# FIDO2AUTH_0021.net
KiCad netlist of a schematic drawn in EAGLE
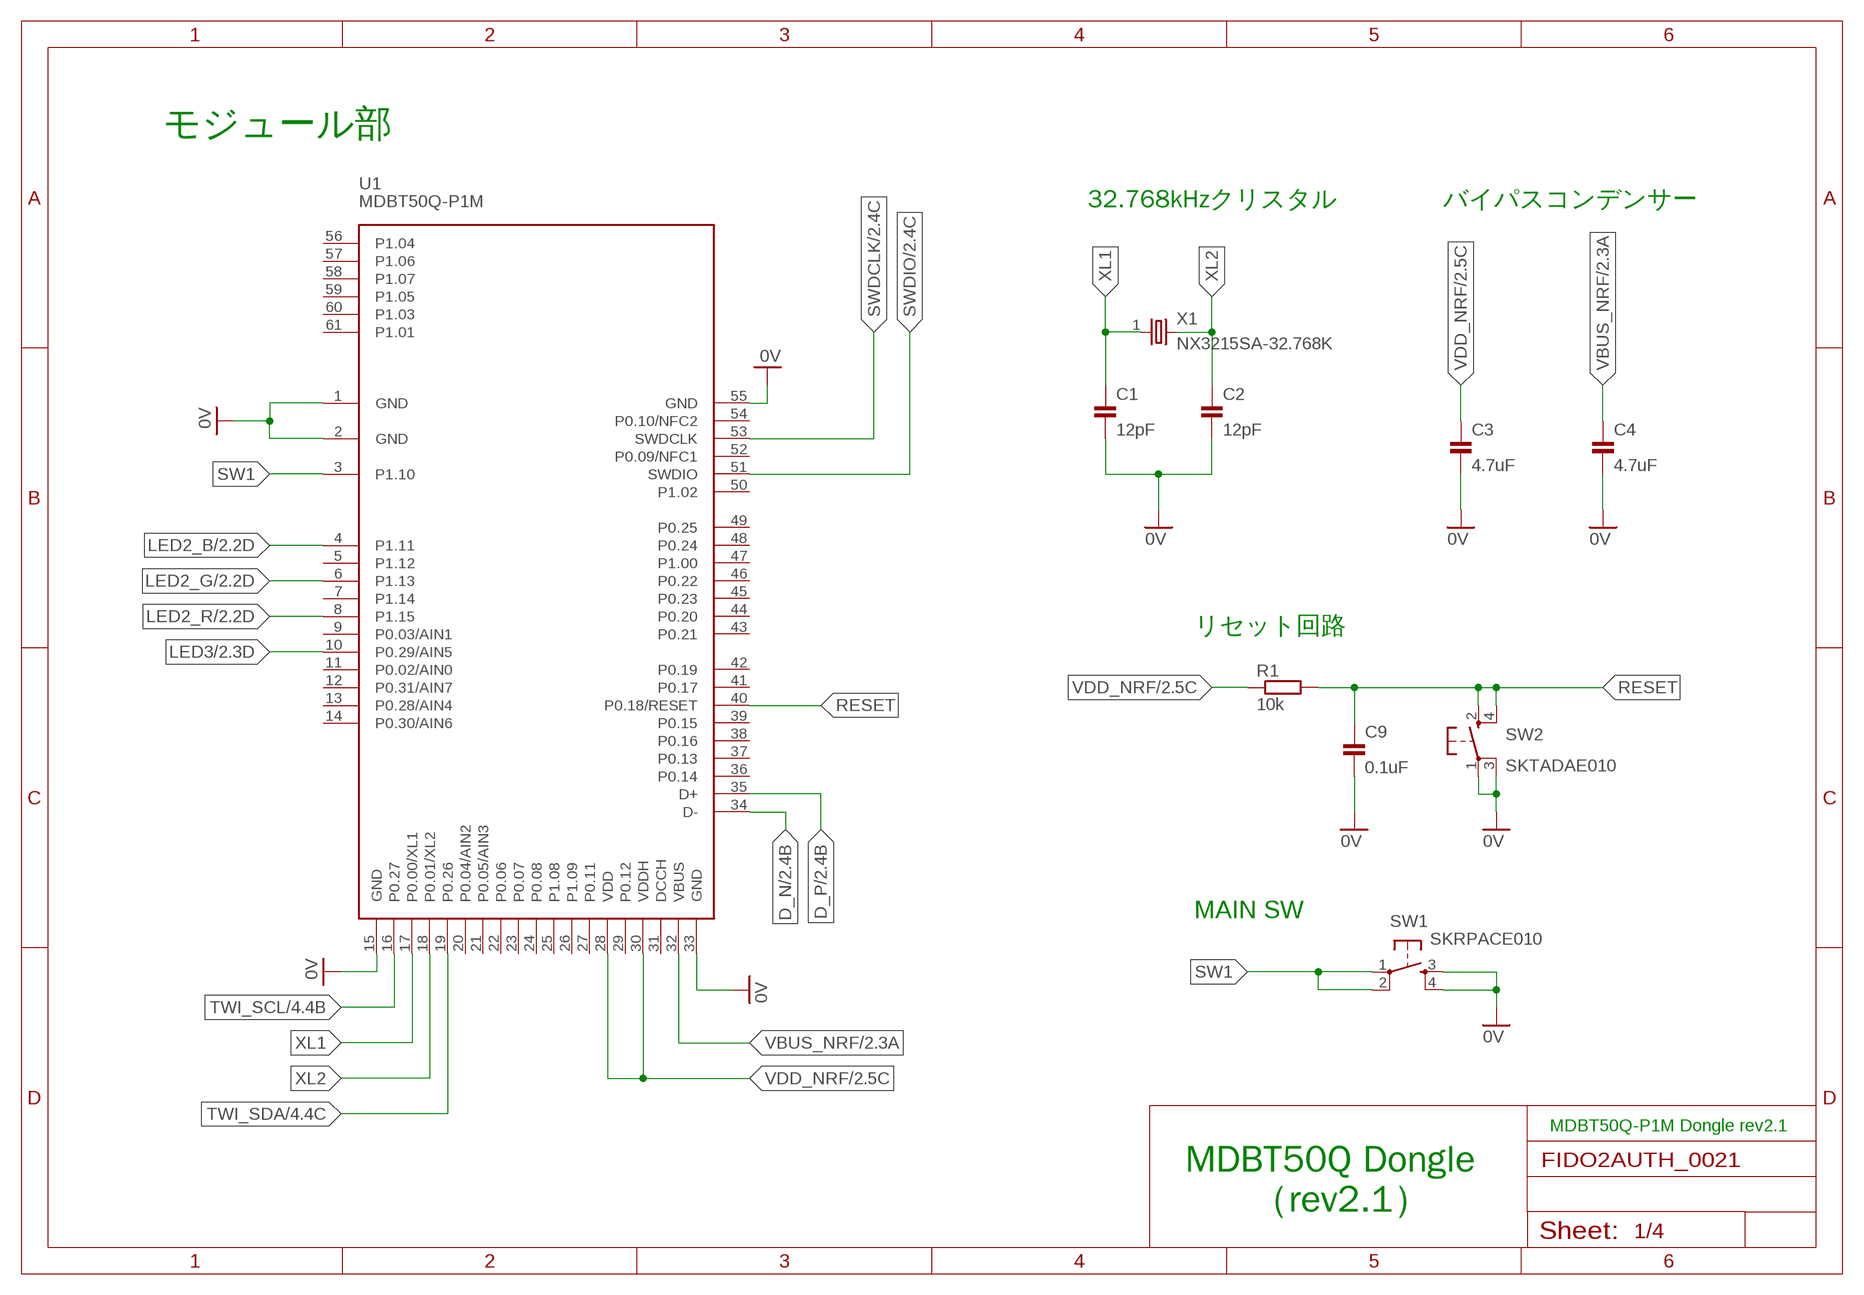
[diagram p0: schematic, sheet 1]
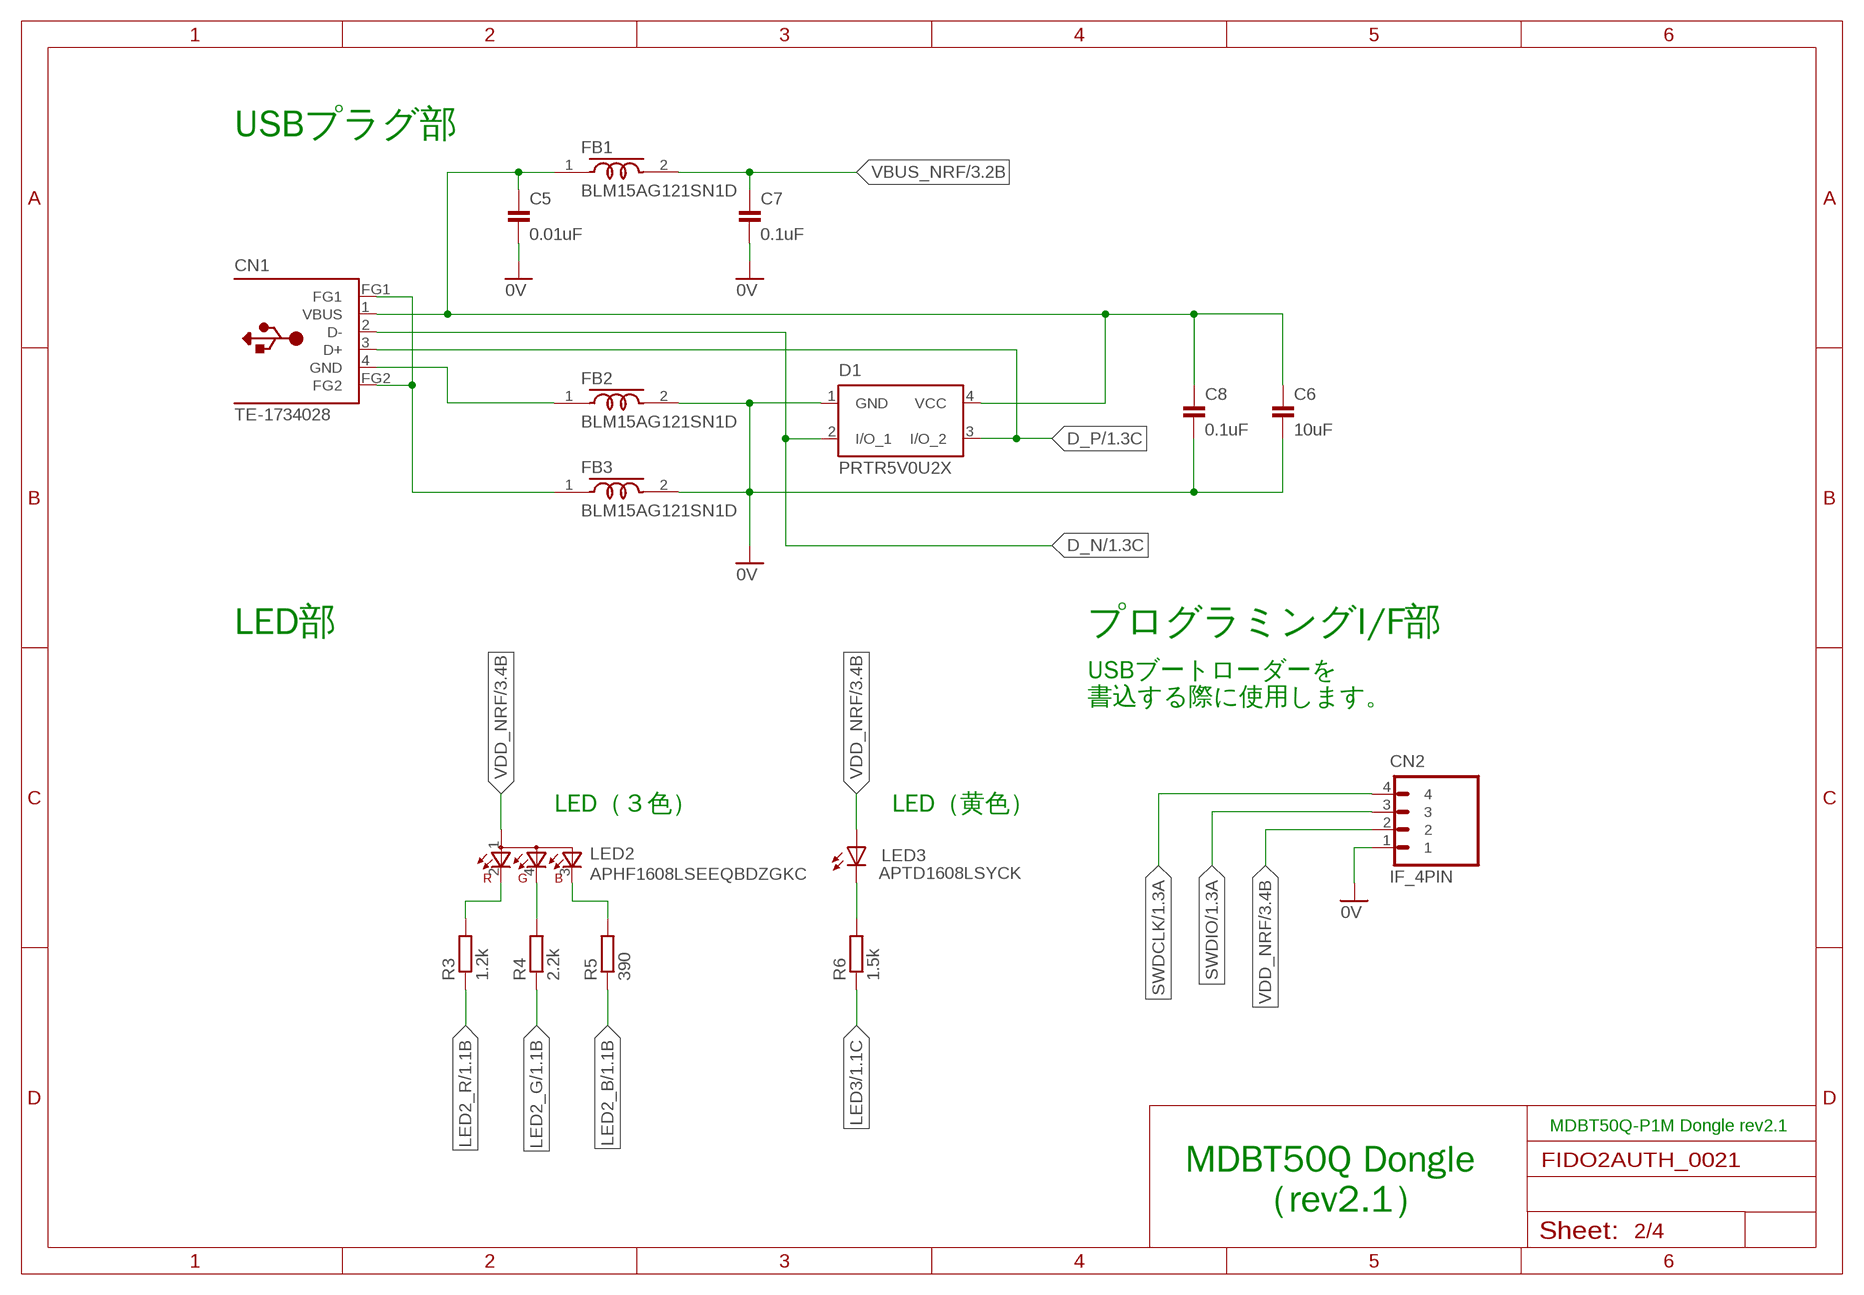
[diagram p1: schematic, sheet 2]
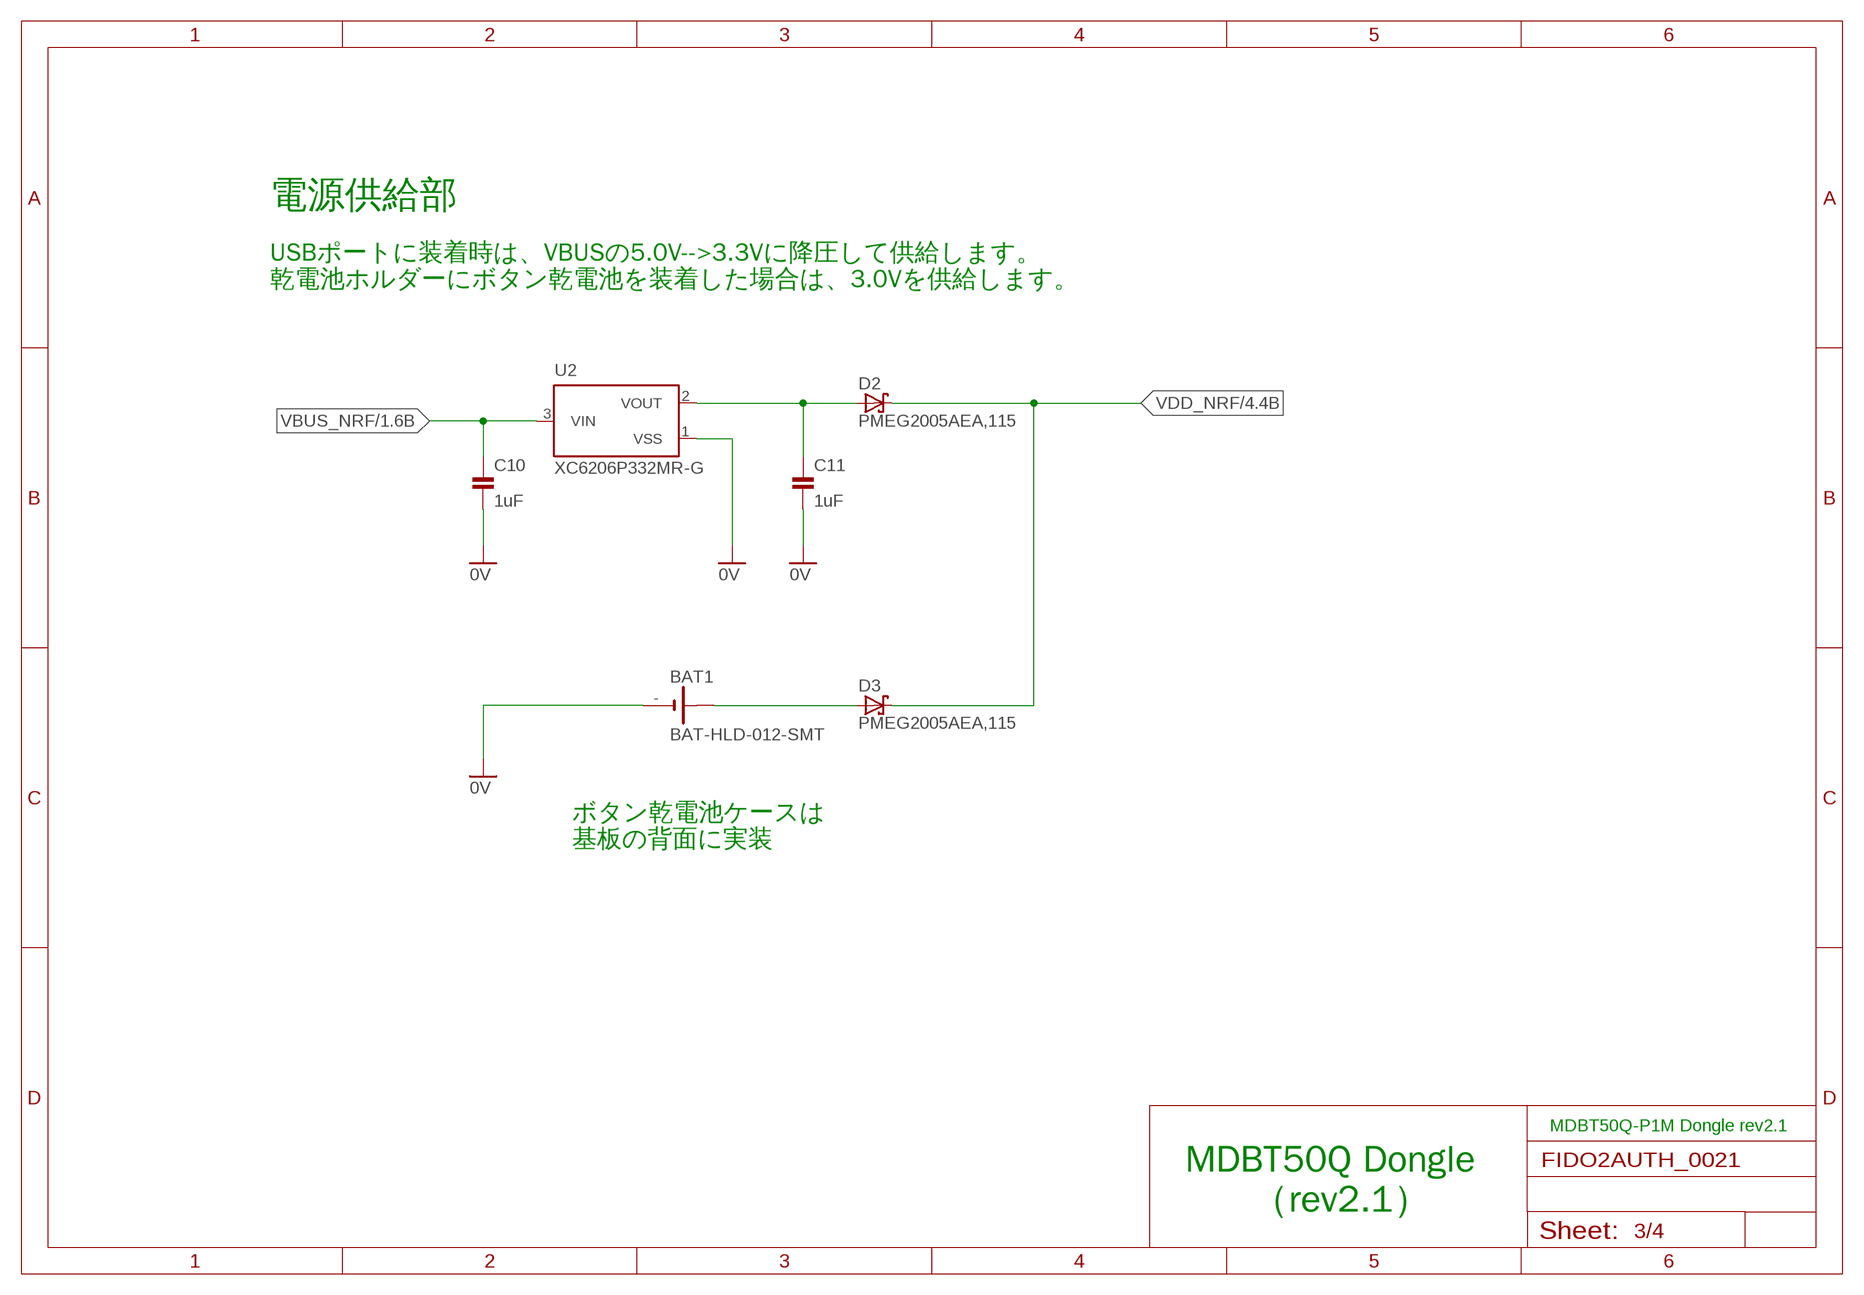
[diagram p2: schematic, sheet 3]
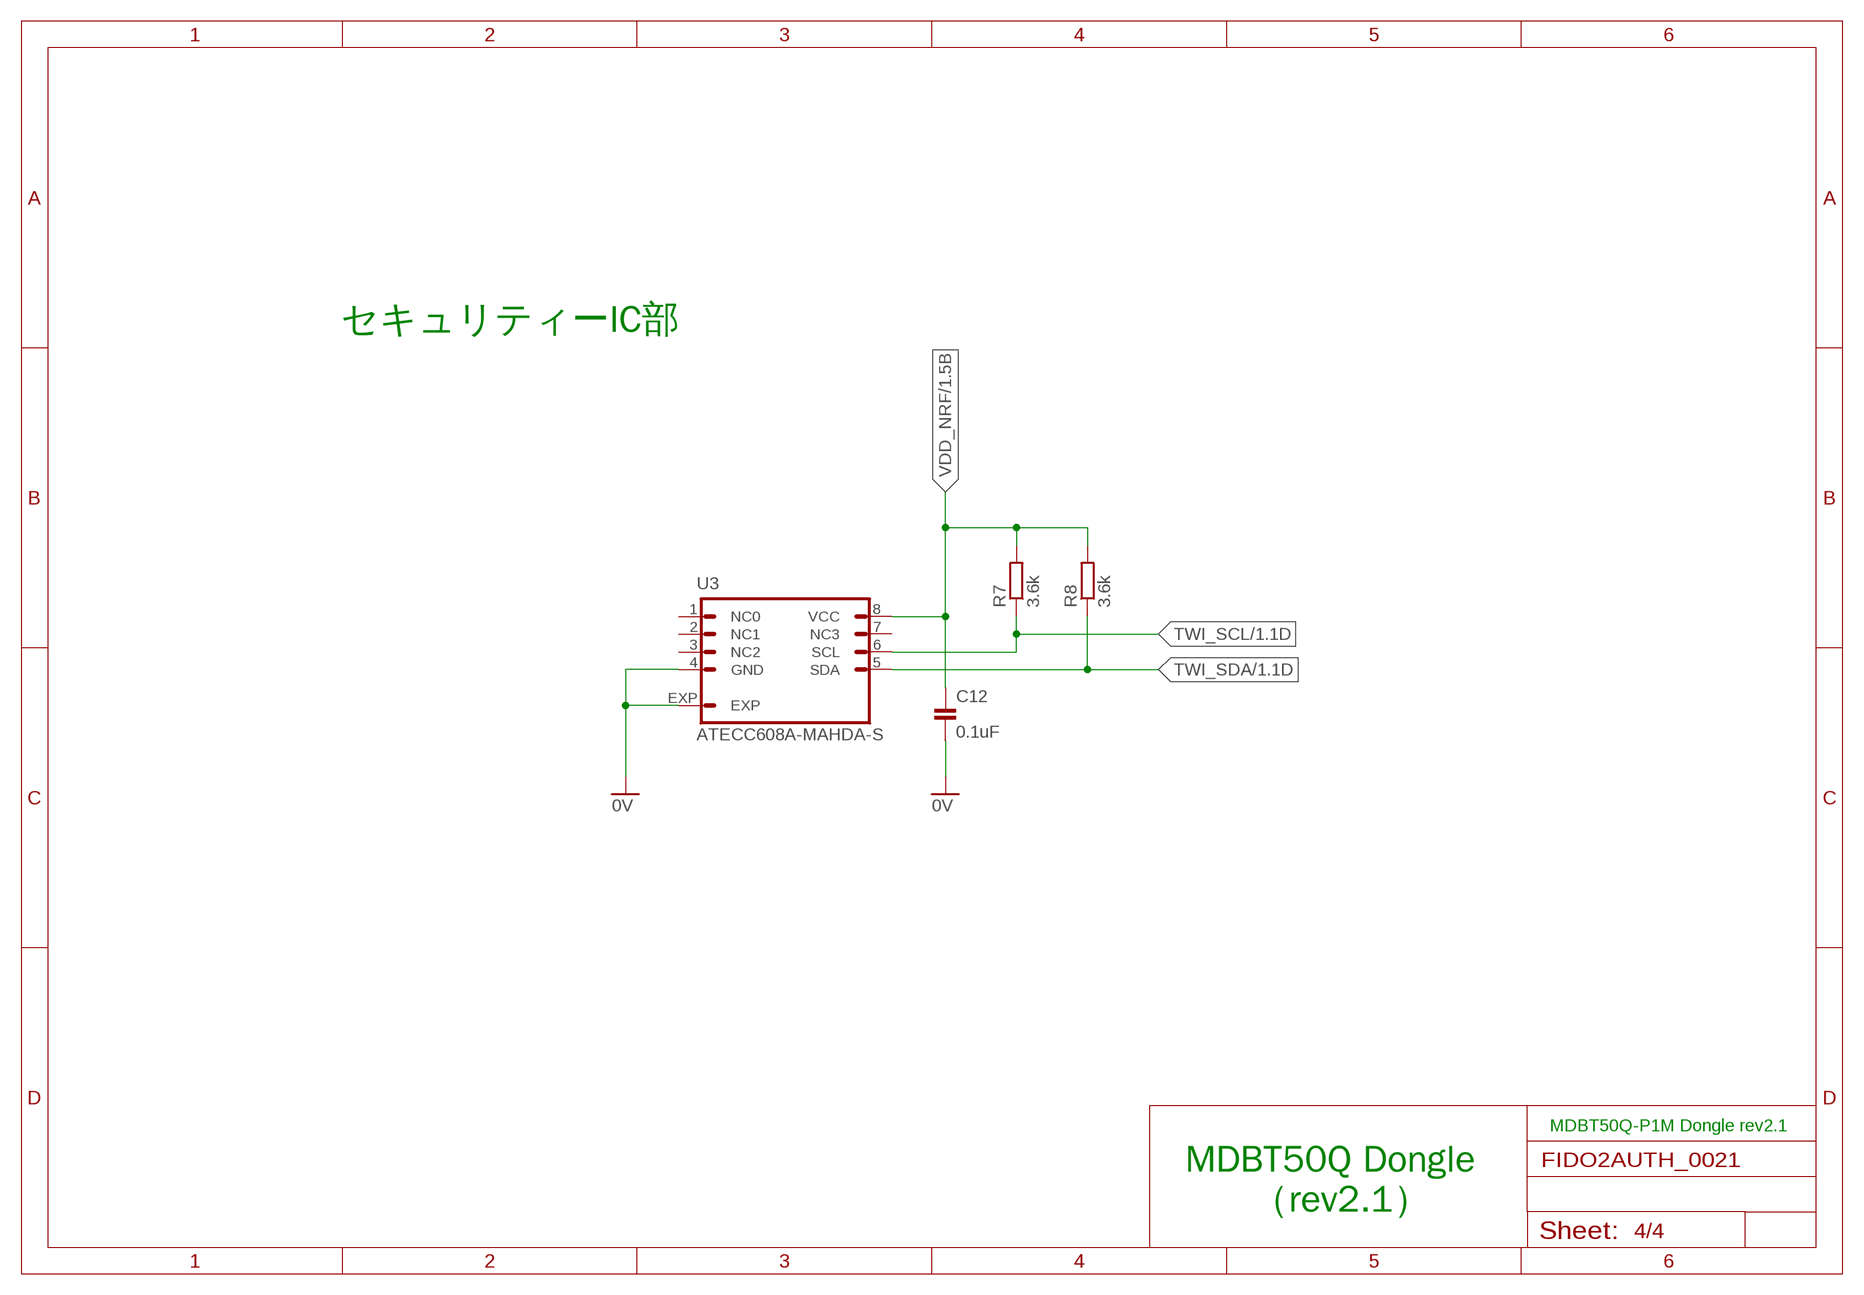
[diagram p3: schematic, sheet 4]

(export (version "E")
  (design (tool "Eeschema 10.0.6"))
  (components
    (comp (ref "C1")
      (value "12pF")
      (footprint "eagle-import:C0603K")
      (libsource (lib "eagle-import") (part "CAP_0603"))
    )
    (comp (ref "C2")
      (value "12pF")
      (footprint "eagle-import:C0603K")
      (libsource (lib "eagle-import") (part "CAP_0603"))
    )
    (comp (ref "C3")
      (value "4.7uF")
      (footprint "eagle-import:C0603K")
      (libsource (lib "eagle-import") (part "CAP_0603"))
    )
    (comp (ref "C4")
      (value "4.7uF")
      (footprint "eagle-import:C0603K")
      (libsource (lib "eagle-import") (part "CAP_0603"))
    )
    (comp (ref "C9")
      (value "0.1uF")
      (footprint "eagle-import:C0402K")
      (libsource (lib "eagle-import") (part "CAP_0402"))
    )
    (comp (ref "R1")
      (value "10k")
      (footprint "eagle-import:R0402")
      (libsource (lib "eagle-import") (part "RESISTOR_0402"))
    )
    (comp (ref "SW1")
      (value "SKRPACE010")
      (footprint "eagle-import:SKRPACE010")
      (libsource (lib "eagle-import") (part "SKRPACE010"))
    )
    (comp (ref "SW2")
      (value "SKTADAE010")
      (footprint "eagle-import:SKTADAE010")
      (libsource (lib "eagle-import") (part "SKTADAE010"))
    )
    (comp (ref "U1")
      (value "MDBT50Q-P1M")
      (footprint "eagle-import:MDBT50Q-P1M")
      (libsource (lib "eagle-import") (part "MDBT50Q-P1M"))
    )
    (comp (ref "X1")
      (value "NX3215SA-32.768K")
      (footprint "eagle-import:NX3215")
      (libsource (lib "eagle-import") (part "NX3215SA-32.768K"))
    )
    (comp (ref "C5")
      (value "0.01uF")
      (footprint "eagle-import:C0402K")
      (libsource (lib "eagle-import") (part "CAP_0402"))
    )
    (comp (ref "C6")
      (value "10uF")
      (footprint "eagle-import:C0603K")
      (libsource (lib "eagle-import") (part "CAP_0603"))
    )
    (comp (ref "C7")
      (value "0.1uF")
      (footprint "eagle-import:C0402K")
      (libsource (lib "eagle-import") (part "CAP_0402"))
    )
    (comp (ref "C8")
      (value "0.1uF")
      (footprint "eagle-import:C0402K")
      (libsource (lib "eagle-import") (part "CAP_0402"))
    )
    (comp (ref "CN1")
      (value "TE-1734028")
      (footprint "eagle-import:TE-1734028")
      (libsource (lib "eagle-import") (part "TE-1734028"))
    )
    (comp (ref "CN2")
      (value "IF_4PIN")
      (footprint "eagle-import:HEADER_4PIN")
      (libsource (lib "eagle-import") (part "IF_4PIN"))
    )
    (comp (ref "D1")
      (value "PRTR5V0U2X")
      (footprint "eagle-import:SOT143B")
      (libsource (lib "eagle-import") (part "PRTR5V0U2X"))
    )
    (comp (ref "FB1")
      (value "BLM15AG121SN1D")
      (footprint "eagle-import:C0402K@1")
      (libsource (lib "eagle-import") (part "BLM15AG121SN1D"))
    )
    (comp (ref "FB2")
      (value "BLM15AG121SN1D")
      (footprint "eagle-import:C0402K@1")
      (libsource (lib "eagle-import") (part "BLM15AG121SN1D"))
    )
    (comp (ref "FB3")
      (value "BLM15AG121SN1D")
      (footprint "eagle-import:C0402K@1")
      (libsource (lib "eagle-import") (part "BLM15AG121SN1D"))
    )
    (comp (ref "LED2")
      (value "APHF1608LSEEQBDZGKC")
      (footprint "eagle-import:APHF1608LSEEQBDZGKC")
      (libsource (lib "eagle-import") (part "APHF1608LSEEQBDZGKC"))
    )
    (comp (ref "LED3")
      (value "APTD1608LSYCK")
      (footprint "eagle-import:CHIPLED_0603")
      (libsource (lib "eagle-import") (part "APTD1608LSYCK"))
    )
    (comp (ref "R3")
      (value "1.2k")
      (footprint "eagle-import:R0402")
      (libsource (lib "eagle-import") (part "RESISTOR_0402"))
    )
    (comp (ref "R4")
      (value "2.2k")
      (footprint "eagle-import:R0402")
      (libsource (lib "eagle-import") (part "RESISTOR_0402"))
    )
    (comp (ref "R5")
      (value "390")
      (footprint "eagle-import:R0402")
      (libsource (lib "eagle-import") (part "RESISTOR_0402"))
    )
    (comp (ref "R6")
      (value "1.5k")
      (footprint "eagle-import:R0402")
      (libsource (lib "eagle-import") (part "RESISTOR_0402"))
    )
    (comp (ref "C12")
      (value "0.1uF")
      (footprint "eagle-import:C0402K")
      (libsource (lib "eagle-import") (part "CAP_0402"))
    )
    (comp (ref "R7")
      (value "3.6k")
      (footprint "eagle-import:R0402")
      (libsource (lib "eagle-import") (part "RESISTOR_0402"))
    )
    (comp (ref "R8")
      (value "3.6k")
      (footprint "eagle-import:R0402")
      (libsource (lib "eagle-import") (part "RESISTOR_0402"))
    )
    (comp (ref "U3")
      (value "ATECC608A-MAHDA-S")
      (footprint "eagle-import:DFN-2X3")
      (libsource (lib "eagle-import") (part "ATECC608A-MAHDA-S"))
    )
    (comp (ref "BAT1")
      (value "BAT-HLD-012-SMT")
      (footprint "eagle-import:BAT-HLD-012-SMT")
      (libsource (lib "eagle-import") (part "BAT-HLD-012-SMT"))
    )
    (comp (ref "C10")
      (value "1uF")
      (footprint "eagle-import:C0603K")
      (libsource (lib "eagle-import") (part "CAP_0603"))
    )
    (comp (ref "C11")
      (value "1uF")
      (footprint "eagle-import:C0603K")
      (libsource (lib "eagle-import") (part "CAP_0603"))
    )
    (comp (ref "D2")
      (value "PMEG2005AEA,115")
      (footprint "eagle-import:SOD323-W")
      (libsource (lib "eagle-import") (part "PMEG2005AEA,115"))
    )
    (comp (ref "D3")
      (value "PMEG2005AEA,115")
      (footprint "eagle-import:SOD323-W")
      (libsource (lib "eagle-import") (part "PMEG2005AEA,115"))
    )
    (comp (ref "U2")
      (value "XC6206P332MR-G")
      (footprint "eagle-import:SOT23")
      (libsource (lib "eagle-import") (part "XC6206P332MR-G"))
    )
  )
  (nets
    (net (code "1") (name "0V") (class "Default")
      (node (ref "BAT1") (pin "-") (pinfunction "-_-") (pintype "passive"))
      (node (ref "C1") (pin "2") (pinfunction "2_2") (pintype "passive"))
      (node (ref "C10") (pin "2") (pinfunction "2_2") (pintype "passive"))
      (node (ref "C11") (pin "2") (pinfunction "2_2") (pintype "passive"))
      (node (ref "C12") (pin "2") (pinfunction "2_2") (pintype "passive"))
      (node (ref "C2") (pin "2") (pinfunction "2_2") (pintype "passive"))
      (node (ref "C3") (pin "2") (pinfunction "2_2") (pintype "passive"))
      (node (ref "C4") (pin "2") (pinfunction "2_2") (pintype "passive"))
      (node (ref "C5") (pin "2") (pinfunction "2_2") (pintype "passive"))
      (node (ref "C6") (pin "2") (pinfunction "2_2") (pintype "passive"))
      (node (ref "C7") (pin "2") (pinfunction "2_2") (pintype "passive"))
      (node (ref "C8") (pin "2") (pinfunction "2_2") (pintype "passive"))
      (node (ref "C9") (pin "2") (pinfunction "2_2") (pintype "passive"))
      (node (ref "CN2") (pin "1") (pinfunction "1_1") (pintype "passive"))
      (node (ref "D1") (pin "1") (pinfunction "GND_1") (pintype "passive"))
      (node (ref "FB2") (pin "2") (pinfunction "2_2") (pintype "passive"))
      (node (ref "FB3") (pin "2") (pinfunction "2_2") (pintype "passive"))
      (node (ref "SW1") (pin "3") (pinfunction "S_3") (pintype "passive"))
      (node (ref "SW1") (pin "4") (pinfunction "S1_4") (pintype "passive"))
      (node (ref "SW2") (pin "1") (pinfunction "P_1") (pintype "passive"))
      (node (ref "SW2") (pin "3") (pinfunction "P1_3") (pintype "passive"))
      (node (ref "U1") (pin "1") (pinfunction "GND_1") (pintype "bidirectional"))
      (node (ref "U1") (pin "15") (pinfunction "GND_15") (pintype "bidirectional"))
      (node (ref "U1") (pin "2") (pinfunction "GND_2") (pintype "bidirectional"))
      (node (ref "U1") (pin "33") (pinfunction "GND_33") (pintype "bidirectional"))
      (node (ref "U1") (pin "55") (pinfunction "GND_55") (pintype "bidirectional"))
      (node (ref "U2") (pin "1") (pinfunction "VSS_1") (pintype "passive"))
      (node (ref "U3") (pin "4") (pinfunction "GND_4") (pintype "passive"))
      (node (ref "U3") (pin "EXP") (pinfunction "EXP_EXP") (pintype "passive"))
    )
    (net (code "2") (name "D_N") (class "Default")
      (node (ref "CN1") (pin "2") (pinfunction "D-_2") (pintype "bidirectional"))
      (node (ref "D1") (pin "2") (pinfunction "I/O_1_2") (pintype "bidirectional"))
      (node (ref "U1") (pin "34") (pinfunction "D-_34") (pintype "bidirectional"))
    )
    (net (code "3") (name "D_P") (class "Default")
      (node (ref "CN1") (pin "3") (pinfunction "D+_3") (pintype "bidirectional"))
      (node (ref "D1") (pin "3") (pinfunction "I/O_2_3") (pintype "bidirectional"))
      (node (ref "U1") (pin "35") (pinfunction "D+_35") (pintype "bidirectional"))
    )
    (net (code "4") (name "LED2_B") (class "Default")
      (node (ref "R5") (pin "1") (pinfunction "1_1") (pintype "passive"))
      (node (ref "U1") (pin "4") (pinfunction "P1.11_4") (pintype "bidirectional"))
    )
    (net (code "5") (name "LED2_G") (class "Default")
      (node (ref "R4") (pin "1") (pinfunction "1_1") (pintype "passive"))
      (node (ref "U1") (pin "6") (pinfunction "P1.13_6") (pintype "bidirectional"))
    )
    (net (code "6") (name "LED2_R") (class "Default")
      (node (ref "R3") (pin "1") (pinfunction "1_1") (pintype "passive"))
      (node (ref "U1") (pin "8") (pinfunction "P1.15_8") (pintype "bidirectional"))
    )
    (net (code "7") (name "LED3") (class "Default")
      (node (ref "R6") (pin "1") (pinfunction "1_1") (pintype "passive"))
      (node (ref "U1") (pin "10") (pinfunction "P0.29/AIN5_10") (pintype "bidirectional"))
    )
    (net (code "8") (name "Net-(BAT1-+)") (class "Default")
      (node (ref "BAT1") (pin "+@1") (pinfunction "+_+@1") (pintype "passive"))
      (node (ref "D3") (pin "A") (pinfunction "A_A") (pintype "passive"))
    )
    (net (code "9") (name "Net-(CN1-GND)") (class "Default")
      (node (ref "CN1") (pin "4") (pinfunction "GND_4") (pintype "passive"))
      (node (ref "FB2") (pin "1") (pinfunction "1_1") (pintype "passive"))
    )
    (net (code "10") (name "Net-(CN1-PadFG1)") (class "Default")
      (node (ref "CN1") (pin "FG1") (pinfunction "FG1_FG1") (pintype "passive"))
      (node (ref "CN1") (pin "FG2") (pinfunction "FG2_FG2") (pintype "passive"))
      (node (ref "FB3") (pin "1") (pinfunction "1_1") (pintype "passive"))
    )
    (net (code "11") (name "Net-(CN1-VBUS)") (class "Default")
      (node (ref "C5") (pin "1") (pinfunction "1_1") (pintype "passive"))
      (node (ref "C6") (pin "1") (pinfunction "1_1") (pintype "passive"))
      (node (ref "C8") (pin "1") (pinfunction "1_1") (pintype "passive"))
      (node (ref "CN1") (pin "1") (pinfunction "VBUS_1") (pintype "passive"))
      (node (ref "D1") (pin "4") (pinfunction "VCC_4") (pintype "passive"))
      (node (ref "FB1") (pin "1") (pinfunction "1_1") (pintype "passive"))
    )
    (net (code "12") (name "Net-(LED2-CBLUE)") (class "Default")
      (node (ref "LED2") (pin "3") (pinfunction "CBLUE_3") (pintype "passive"))
      (node (ref "R5") (pin "2") (pinfunction "2_2") (pintype "passive"))
    )
    (net (code "13") (name "Net-(LED2-CGREEN)") (class "Default")
      (node (ref "LED2") (pin "4") (pinfunction "CGREEN_4") (pintype "passive"))
      (node (ref "R4") (pin "2") (pinfunction "2_2") (pintype "passive"))
    )
    (net (code "14") (name "Net-(LED2-CRED)") (class "Default")
      (node (ref "LED2") (pin "2") (pinfunction "CRED_2") (pintype "passive"))
      (node (ref "R3") (pin "2") (pinfunction "2_2") (pintype "passive"))
    )
    (net (code "15") (name "Net-(LED3-PadC)") (class "Default")
      (node (ref "LED3") (pin "C") (pinfunction "C_C") (pintype "passive"))
      (node (ref "R6") (pin "2") (pinfunction "2_2") (pintype "passive"))
    )
    (net (code "16") (name "Net-(U2-VOUT)") (class "Default")
      (node (ref "C11") (pin "1") (pinfunction "1_1") (pintype "passive"))
      (node (ref "D2") (pin "A") (pinfunction "A_A") (pintype "passive"))
      (node (ref "U2") (pin "2") (pinfunction "VOUT_2") (pintype "passive"))
    )
    (net (code "17") (name "RESET") (class "Default")
      (node (ref "C9") (pin "1") (pinfunction "1_1") (pintype "passive"))
      (node (ref "R1") (pin "2") (pinfunction "2_2") (pintype "passive"))
      (node (ref "SW2") (pin "2") (pinfunction "S_2") (pintype "passive"))
      (node (ref "SW2") (pin "4") (pinfunction "S1_4") (pintype "passive"))
      (node (ref "U1") (pin "40") (pinfunction "P0.18/RESET_40") (pintype "bidirectional"))
    )
    (net (code "18") (name "SW1") (class "Default")
      (node (ref "SW1") (pin "1") (pinfunction "P_1") (pintype "passive"))
      (node (ref "SW1") (pin "2") (pinfunction "P1_2") (pintype "passive"))
      (node (ref "U1") (pin "3") (pinfunction "P1.10_3") (pintype "bidirectional"))
    )
    (net (code "19") (name "SWDCLK") (class "Default")
      (node (ref "CN2") (pin "4") (pinfunction "4_4") (pintype "passive"))
      (node (ref "U1") (pin "53") (pinfunction "SWDCLK_53") (pintype "bidirectional"))
    )
    (net (code "20") (name "SWDIO") (class "Default")
      (node (ref "CN2") (pin "3") (pinfunction "3_3") (pintype "passive"))
      (node (ref "U1") (pin "51") (pinfunction "SWDIO_51") (pintype "bidirectional"))
    )
    (net (code "21") (name "TWI_SCL") (class "Default")
      (node (ref "R7") (pin "1") (pinfunction "1_1") (pintype "passive"))
      (node (ref "U1") (pin "16") (pinfunction "P0.27_16") (pintype "bidirectional"))
      (node (ref "U3") (pin "6") (pinfunction "SCL_6") (pintype "bidirectional"))
    )
    (net (code "22") (name "TWI_SDA") (class "Default")
      (node (ref "R8") (pin "1") (pinfunction "1_1") (pintype "passive"))
      (node (ref "U1") (pin "19") (pinfunction "P0.26_19") (pintype "bidirectional"))
      (node (ref "U3") (pin "5") (pinfunction "SDA_5") (pintype "bidirectional"))
    )
    (net (code "23") (name "VBUS_NRF") (class "Default")
      (node (ref "C10") (pin "1") (pinfunction "1_1") (pintype "passive"))
      (node (ref "C4") (pin "1") (pinfunction "1_1") (pintype "passive"))
      (node (ref "C7") (pin "1") (pinfunction "1_1") (pintype "passive"))
      (node (ref "FB1") (pin "2") (pinfunction "2_2") (pintype "passive"))
      (node (ref "U1") (pin "32") (pinfunction "VBUS_32") (pintype "bidirectional"))
      (node (ref "U2") (pin "3") (pinfunction "VIN_3") (pintype "passive"))
    )
    (net (code "24") (name "VDD_NRF") (class "Default")
      (node (ref "C12") (pin "1") (pinfunction "1_1") (pintype "passive"))
      (node (ref "C3") (pin "1") (pinfunction "1_1") (pintype "passive"))
      (node (ref "CN2") (pin "2") (pinfunction "2_2") (pintype "passive"))
      (node (ref "D2") (pin "C") (pinfunction "C_C") (pintype "passive"))
      (node (ref "D3") (pin "C") (pinfunction "C_C") (pintype "passive"))
      (node (ref "LED2") (pin "1") (pinfunction "A_1") (pintype "passive"))
      (node (ref "LED3") (pin "A") (pinfunction "A_A") (pintype "passive"))
      (node (ref "R1") (pin "1") (pinfunction "1_1") (pintype "passive"))
      (node (ref "R7") (pin "2") (pinfunction "2_2") (pintype "passive"))
      (node (ref "R8") (pin "2") (pinfunction "2_2") (pintype "passive"))
      (node (ref "U1") (pin "28") (pinfunction "VDD_28") (pintype "bidirectional"))
      (node (ref "U1") (pin "30") (pinfunction "VDDH_30") (pintype "bidirectional"))
      (node (ref "U3") (pin "8") (pinfunction "VCC_8") (pintype "passive"))
    )
    (net (code "25") (name "XL1") (class "Default")
      (node (ref "C1") (pin "1") (pinfunction "1_1") (pintype "passive"))
      (node (ref "U1") (pin "17") (pinfunction "P0.00/XL1_17") (pintype "bidirectional"))
      (node (ref "X1") (pin "1") (pinfunction "1_1") (pintype "passive"))
    )
    (net (code "26") (name "XL2") (class "Default")
      (node (ref "C2") (pin "1") (pinfunction "1_1") (pintype "passive"))
      (node (ref "U1") (pin "18") (pinfunction "P0.01/XL2_18") (pintype "bidirectional"))
      (node (ref "X1") (pin "2") (pinfunction "2_2") (pintype "passive"))
    )
    (net (code "27") (name "unconnected-(U1-DCCH-Pad31)") (class "Default")
      (node (ref "U1") (pin "31") (pinfunction "DCCH_31") (pintype "bidirectional"))
    )
    (net (code "28") (name "unconnected-(U1-P0.02{slash}AIN0-Pad11)") (class "Default")
      (node (ref "U1") (pin "11") (pinfunction "P0.02/AIN0_11") (pintype "bidirectional"))
    )
    (net (code "29") (name "unconnected-(U1-P0.03{slash}AIN1-Pad9)") (class "Default")
      (node (ref "U1") (pin "9") (pinfunction "P0.03/AIN1_9") (pintype "bidirectional"))
    )
    (net (code "30") (name "unconnected-(U1-P0.04{slash}AIN2-Pad20)") (class "Default")
      (node (ref "U1") (pin "20") (pinfunction "P0.04/AIN2_20") (pintype "bidirectional"))
    )
    (net (code "31") (name "unconnected-(U1-P0.05{slash}AIN3-Pad21)") (class "Default")
      (node (ref "U1") (pin "21") (pinfunction "P0.05/AIN3_21") (pintype "bidirectional"))
    )
    (net (code "32") (name "unconnected-(U1-P0.06-Pad22)") (class "Default")
      (node (ref "U1") (pin "22") (pinfunction "P0.06_22") (pintype "bidirectional"))
    )
    (net (code "33") (name "unconnected-(U1-P0.07-Pad23)") (class "Default")
      (node (ref "U1") (pin "23") (pinfunction "P0.07_23") (pintype "bidirectional"))
    )
    (net (code "34") (name "unconnected-(U1-P0.08-Pad24)") (class "Default")
      (node (ref "U1") (pin "24") (pinfunction "P0.08_24") (pintype "bidirectional"))
    )
    (net (code "35") (name "unconnected-(U1-P0.09{slash}NFC1-Pad52)") (class "Default")
      (node (ref "U1") (pin "52") (pinfunction "P0.09/NFC1_52") (pintype "bidirectional"))
    )
    (net (code "36") (name "unconnected-(U1-P0.10{slash}NFC2-Pad54)") (class "Default")
      (node (ref "U1") (pin "54") (pinfunction "P0.10/NFC2_54") (pintype "bidirectional"))
    )
    (net (code "37") (name "unconnected-(U1-P0.11-Pad27)") (class "Default")
      (node (ref "U1") (pin "27") (pinfunction "P0.11_27") (pintype "bidirectional"))
    )
    (net (code "38") (name "unconnected-(U1-P0.12-Pad29)") (class "Default")
      (node (ref "U1") (pin "29") (pinfunction "P0.12_29") (pintype "bidirectional"))
    )
    (net (code "39") (name "unconnected-(U1-P0.13-Pad37)") (class "Default")
      (node (ref "U1") (pin "37") (pinfunction "P0.13_37") (pintype "bidirectional"))
    )
    (net (code "40") (name "unconnected-(U1-P0.14-Pad36)") (class "Default")
      (node (ref "U1") (pin "36") (pinfunction "P0.14_36") (pintype "bidirectional"))
    )
    (net (code "41") (name "unconnected-(U1-P0.15-Pad39)") (class "Default")
      (node (ref "U1") (pin "39") (pinfunction "P0.15_39") (pintype "bidirectional"))
    )
    (net (code "42") (name "unconnected-(U1-P0.16-Pad38)") (class "Default")
      (node (ref "U1") (pin "38") (pinfunction "P0.16_38") (pintype "bidirectional"))
    )
    (net (code "43") (name "unconnected-(U1-P0.17-Pad41)") (class "Default")
      (node (ref "U1") (pin "41") (pinfunction "P0.17_41") (pintype "bidirectional"))
    )
    (net (code "44") (name "unconnected-(U1-P0.19-Pad42)") (class "Default")
      (node (ref "U1") (pin "42") (pinfunction "P0.19_42") (pintype "bidirectional"))
    )
    (net (code "45") (name "unconnected-(U1-P0.20-Pad44)") (class "Default")
      (node (ref "U1") (pin "44") (pinfunction "P0.20_44") (pintype "bidirectional"))
    )
    (net (code "46") (name "unconnected-(U1-P0.21-Pad43)") (class "Default")
      (node (ref "U1") (pin "43") (pinfunction "P0.21_43") (pintype "bidirectional"))
    )
    (net (code "47") (name "unconnected-(U1-P0.22-Pad46)") (class "Default")
      (node (ref "U1") (pin "46") (pinfunction "P0.22_46") (pintype "bidirectional"))
    )
    (net (code "48") (name "unconnected-(U1-P0.23-Pad45)") (class "Default")
      (node (ref "U1") (pin "45") (pinfunction "P0.23_45") (pintype "bidirectional"))
    )
    (net (code "49") (name "unconnected-(U1-P0.24-Pad48)") (class "Default")
      (node (ref "U1") (pin "48") (pinfunction "P0.24_48") (pintype "bidirectional"))
    )
    (net (code "50") (name "unconnected-(U1-P0.25-Pad49)") (class "Default")
      (node (ref "U1") (pin "49") (pinfunction "P0.25_49") (pintype "bidirectional"))
    )
    (net (code "51") (name "unconnected-(U1-P0.28{slash}AIN4-Pad13)") (class "Default")
      (node (ref "U1") (pin "13") (pinfunction "P0.28/AIN4_13") (pintype "bidirectional"))
    )
    (net (code "52") (name "unconnected-(U1-P0.30{slash}AIN6-Pad14)") (class "Default")
      (node (ref "U1") (pin "14") (pinfunction "P0.30/AIN6_14") (pintype "bidirectional"))
    )
    (net (code "53") (name "unconnected-(U1-P0.31{slash}AIN7-Pad12)") (class "Default")
      (node (ref "U1") (pin "12") (pinfunction "P0.31/AIN7_12") (pintype "bidirectional"))
    )
    (net (code "54") (name "unconnected-(U1-P1.00-Pad47)") (class "Default")
      (node (ref "U1") (pin "47") (pinfunction "P1.00_47") (pintype "bidirectional"))
    )
    (net (code "55") (name "unconnected-(U1-P1.01-Pad61)") (class "Default")
      (node (ref "U1") (pin "61") (pinfunction "P1.01_61") (pintype "bidirectional"))
    )
    (net (code "56") (name "unconnected-(U1-P1.02-Pad50)") (class "Default")
      (node (ref "U1") (pin "50") (pinfunction "P1.02_50") (pintype "bidirectional"))
    )
    (net (code "57") (name "unconnected-(U1-P1.03-Pad60)") (class "Default")
      (node (ref "U1") (pin "60") (pinfunction "P1.03_60") (pintype "bidirectional"))
    )
    (net (code "58") (name "unconnected-(U1-P1.04-Pad56)") (class "Default")
      (node (ref "U1") (pin "56") (pinfunction "P1.04_56") (pintype "bidirectional"))
    )
    (net (code "59") (name "unconnected-(U1-P1.05-Pad59)") (class "Default")
      (node (ref "U1") (pin "59") (pinfunction "P1.05_59") (pintype "bidirectional"))
    )
    (net (code "60") (name "unconnected-(U1-P1.06-Pad57)") (class "Default")
      (node (ref "U1") (pin "57") (pinfunction "P1.06_57") (pintype "bidirectional"))
    )
    (net (code "61") (name "unconnected-(U1-P1.07-Pad58)") (class "Default")
      (node (ref "U1") (pin "58") (pinfunction "P1.07_58") (pintype "bidirectional"))
    )
    (net (code "62") (name "unconnected-(U1-P1.08-Pad25)") (class "Default")
      (node (ref "U1") (pin "25") (pinfunction "P1.08_25") (pintype "bidirectional"))
    )
    (net (code "63") (name "unconnected-(U1-P1.09-Pad26)") (class "Default")
      (node (ref "U1") (pin "26") (pinfunction "P1.09_26") (pintype "bidirectional"))
    )
    (net (code "64") (name "unconnected-(U1-P1.12-Pad5)") (class "Default")
      (node (ref "U1") (pin "5") (pinfunction "P1.12_5") (pintype "bidirectional"))
    )
    (net (code "65") (name "unconnected-(U1-P1.14-Pad7)") (class "Default")
      (node (ref "U1") (pin "7") (pinfunction "P1.14_7") (pintype "bidirectional"))
    )
    (net (code "66") (name "unconnected-(U3-NC0-Pad1)") (class "Default")
      (node (ref "U3") (pin "1") (pinfunction "NC0_1") (pintype "passive"))
    )
    (net (code "67") (name "unconnected-(U3-NC1-Pad2)") (class "Default")
      (node (ref "U3") (pin "2") (pinfunction "NC1_2") (pintype "passive"))
    )
    (net (code "68") (name "unconnected-(U3-NC2-Pad3)") (class "Default")
      (node (ref "U3") (pin "3") (pinfunction "NC2_3") (pintype "passive"))
    )
    (net (code "69") (name "unconnected-(U3-NC3-Pad7)") (class "Default")
      (node (ref "U3") (pin "7") (pinfunction "NC3_7") (pintype "passive"))
    )
  )
)
